# gaius.net
KiCad netlist of a schematic drawn in EAGLE
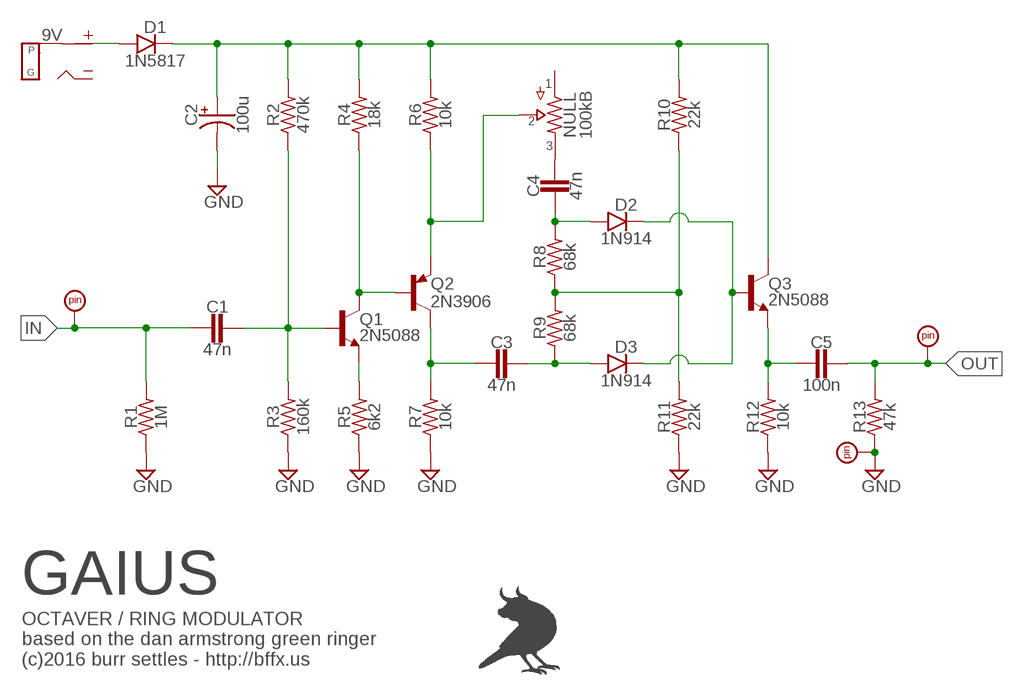
[diagram p0: schematic, sheet 1]

(export (version "E")
  (design (tool "Eeschema 10.0.6"))
  (components
    (comp (ref "9V")
      (value "DC_MONO")
      (footprint "eagle-import:DC")
      (libsource (lib "eagle-import") (part "DC_MONO"))
    )
    (comp (ref "C1")
      (value "47n")
      (footprint "eagle-import:050X030_025_2")
      (libsource (lib "eagle-import") (part "CER/FILM2"))
    )
    (comp (ref "C2")
      (value "100u")
      (footprint "eagle-import:050_020_1")
      (libsource (lib "eagle-import") (part "0501"))
    )
    (comp (ref "C3")
      (value "47n")
      (footprint "eagle-import:050X030_025_2")
      (libsource (lib "eagle-import") (part "CER/FILM2"))
    )
    (comp (ref "C4")
      (value "47n")
      (footprint "eagle-import:050X030_025_2")
      (libsource (lib "eagle-import") (part "CER/FILM2"))
    )
    (comp (ref "C5")
      (value "100n")
      (footprint "eagle-import:050X030_025_2")
      (libsource (lib "eagle-import") (part "CER/FILM2"))
    )
    (comp (ref "D1")
      (value "1N5817")
      (footprint "eagle-import:DO41-3")
      (libsource (lib "eagle-import") (part "DO41.3"))
    )
    (comp (ref "D2")
      (value "1N914")
      (footprint "eagle-import:DO35-2")
      (libsource (lib "eagle-import") (part "DO35.2"))
    )
    (comp (ref "D3")
      (value "1N914")
      (footprint "eagle-import:DO35-2")
      (libsource (lib "eagle-import") (part "DO35.2"))
    )
    (comp (ref "GND")
      (value "PADRND")
      (footprint "eagle-import:ROUND")
      (libsource (lib "eagle-import") (part "PADRND"))
    )
    (comp (ref "IN")
      (value "PADSQR")
      (footprint "eagle-import:SQUARE")
      (libsource (lib "eagle-import") (part "PADSQR"))
    )
    (comp (ref "NULL")
      (value "100kB")
      (footprint "eagle-import:2262_TRIM")
      (libsource (lib "eagle-import") (part "POTSTRIM"))
    )
    (comp (ref "OUT")
      (value "PADSQR")
      (footprint "eagle-import:SQUARE")
      (libsource (lib "eagle-import") (part "PADSQR"))
    )
    (comp (ref "Q1")
      (value "2N5088")
      (footprint "eagle-import:TO92-")
      (libsource (lib "eagle-import") (part "2N5088"))
    )
    (comp (ref "Q2")
      (value "2N3906")
      (footprint "eagle-import:TO92-")
      (libsource (lib "eagle-import") (part "2N3906-"))
    )
    (comp (ref "Q3")
      (value "2N5088")
      (footprint "eagle-import:TO92-")
      (libsource (lib "eagle-import") (part "2N5088"))
    )
    (comp (ref "R1")
      (value "1M")
      (footprint "eagle-import:R0207_3")
      (libsource (lib "eagle-import") (part "R_.3B"))
    )
    (comp (ref "R2")
      (value "470k")
      (footprint "eagle-import:R0207_3")
      (libsource (lib "eagle-import") (part "R_.3B"))
    )
    (comp (ref "R3")
      (value "160k")
      (footprint "eagle-import:R0207_3")
      (libsource (lib "eagle-import") (part "R_.3B"))
    )
    (comp (ref "R4")
      (value "18k")
      (footprint "eagle-import:R0207_3")
      (libsource (lib "eagle-import") (part "R_.3B"))
    )
    (comp (ref "R5")
      (value "6k2")
      (footprint "eagle-import:R0207_3")
      (libsource (lib "eagle-import") (part "R_.3B"))
    )
    (comp (ref "R6")
      (value "10k")
      (footprint "eagle-import:R0207_3")
      (libsource (lib "eagle-import") (part "R_.3B"))
    )
    (comp (ref "R7")
      (value "10k")
      (footprint "eagle-import:R0207_3")
      (libsource (lib "eagle-import") (part "R_.3B"))
    )
    (comp (ref "R8")
      (value "68k")
      (footprint "eagle-import:R0207_3")
      (libsource (lib "eagle-import") (part "R_.3B"))
    )
    (comp (ref "R9")
      (value "68k")
      (footprint "eagle-import:R0207_3")
      (libsource (lib "eagle-import") (part "R_.3B"))
    )
    (comp (ref "R10")
      (value "22k")
      (footprint "eagle-import:R0207_3")
      (libsource (lib "eagle-import") (part "R_.3B"))
    )
    (comp (ref "R11")
      (value "22k")
      (footprint "eagle-import:R0207_3")
      (libsource (lib "eagle-import") (part "R_.3B"))
    )
    (comp (ref "R12")
      (value "10k")
      (footprint "eagle-import:R0207_3")
      (libsource (lib "eagle-import") (part "R_.3B"))
    )
    (comp (ref "R13")
      (value "47k")
      (footprint "eagle-import:R0207_3")
      (libsource (lib "eagle-import") (part "R_.3B"))
    )
  )
  (nets
    (net (code "1") (name "GND") (class "Default")
      (node (ref "C2") (pin "-") (pinfunction "-_-") (pintype "passive"))
      (node (ref "GND") (pin "1") (pinfunction "P$1_1") (pintype "bidirectional"))
      (node (ref "R1") (pin "1") (pinfunction "1_1") (pintype "passive"))
      (node (ref "R11") (pin "1") (pinfunction "1_1") (pintype "passive"))
      (node (ref "R12") (pin "1") (pinfunction "1_1") (pintype "passive"))
      (node (ref "R13") (pin "1") (pinfunction "1_1") (pintype "passive"))
      (node (ref "R3") (pin "1") (pinfunction "1_1") (pintype "passive"))
      (node (ref "R5") (pin "1") (pinfunction "1_1") (pintype "passive"))
      (node (ref "R7") (pin "1") (pinfunction "1_1") (pintype "passive"))
    )
    (net (code "2") (name "IN") (class "Default")
      (node (ref "C1") (pin "2") (pinfunction "2_2") (pintype "passive"))
      (node (ref "IN") (pin "1") (pinfunction "P$1_1") (pintype "bidirectional"))
      (node (ref "R1") (pin "2") (pinfunction "2_2") (pintype "passive"))
    )
    (net (code "3") (name "Net-(9V-TIP)") (class "Default")
      (node (ref "9V") (pin "T") (pinfunction "TIP_T") (pintype "passive"))
      (node (ref "D1") (pin "A") (pinfunction "A_A") (pintype "passive"))
    )
    (net (code "4") (name "Net-(C3-Pad1)") (class "Default")
      (node (ref "C3") (pin "1") (pinfunction "1_1") (pintype "passive"))
      (node (ref "D3") (pin "A") (pinfunction "A_A") (pintype "passive"))
      (node (ref "R9") (pin "1") (pinfunction "1_1") (pintype "passive"))
    )
    (net (code "5") (name "Net-(C4-Pad1)") (class "Default")
      (node (ref "C4") (pin "1") (pinfunction "1_1") (pintype "passive"))
      (node (ref "NULL") (pin "3") (pinfunction "3_3") (pintype "passive"))
    )
    (net (code "6") (name "Net-(C4-Pad2)") (class "Default")
      (node (ref "C4") (pin "2") (pinfunction "2_2") (pintype "passive"))
      (node (ref "D2") (pin "A") (pinfunction "A_A") (pintype "passive"))
      (node (ref "R8") (pin "2") (pinfunction "2_2") (pintype "passive"))
    )
    (net (code "7") (name "Net-(Q1-B)") (class "Default")
      (node (ref "C1") (pin "1") (pinfunction "1_1") (pintype "passive"))
      (node (ref "Q1") (pin "2") (pinfunction "B_2") (pintype "passive"))
      (node (ref "R2") (pin "1") (pinfunction "1_1") (pintype "passive"))
      (node (ref "R3") (pin "2") (pinfunction "2_2") (pintype "passive"))
    )
    (net (code "8") (name "Net-(Q1-C)") (class "Default")
      (node (ref "Q1") (pin "1") (pinfunction "C_1") (pintype "passive"))
      (node (ref "Q2") (pin "2") (pinfunction "B_2") (pintype "passive"))
      (node (ref "R4") (pin "1") (pinfunction "1_1") (pintype "passive"))
    )
    (net (code "9") (name "Net-(Q1-E)") (class "Default")
      (node (ref "Q1") (pin "3") (pinfunction "E_3") (pintype "passive"))
      (node (ref "R5") (pin "2") (pinfunction "2_2") (pintype "passive"))
    )
    (net (code "10") (name "Net-(Q2-C)") (class "Default")
      (node (ref "C3") (pin "2") (pinfunction "2_2") (pintype "passive"))
      (node (ref "Q2") (pin "1") (pinfunction "C_1") (pintype "passive"))
      (node (ref "R7") (pin "2") (pinfunction "2_2") (pintype "passive"))
    )
    (net (code "11") (name "Net-(Q2-E)") (class "Default")
      (node (ref "NULL") (pin "2") (pinfunction "2_2") (pintype "passive"))
      (node (ref "Q2") (pin "3") (pinfunction "E_3") (pintype "passive"))
      (node (ref "R6") (pin "1") (pinfunction "1_1") (pintype "passive"))
    )
    (net (code "12") (name "Net-(Q3-B)") (class "Default")
      (node (ref "D2") (pin "C") (pinfunction "C_C") (pintype "passive"))
      (node (ref "D3") (pin "C") (pinfunction "C_C") (pintype "passive"))
      (node (ref "Q3") (pin "2") (pinfunction "B_2") (pintype "passive"))
    )
    (net (code "13") (name "Net-(Q3-C)") (class "Default")
      (node (ref "C2") (pin "+") (pinfunction "+_+") (pintype "passive"))
      (node (ref "D1") (pin "C") (pinfunction "C_C") (pintype "passive"))
      (node (ref "Q3") (pin "1") (pinfunction "C_1") (pintype "passive"))
      (node (ref "R10") (pin "2") (pinfunction "2_2") (pintype "passive"))
      (node (ref "R2") (pin "2") (pinfunction "2_2") (pintype "passive"))
      (node (ref "R4") (pin "2") (pinfunction "2_2") (pintype "passive"))
      (node (ref "R6") (pin "2") (pinfunction "2_2") (pintype "passive"))
    )
    (net (code "14") (name "Net-(Q3-E)") (class "Default")
      (node (ref "C5") (pin "2") (pinfunction "2_2") (pintype "passive"))
      (node (ref "Q3") (pin "3") (pinfunction "E_3") (pintype "passive"))
      (node (ref "R12") (pin "2") (pinfunction "2_2") (pintype "passive"))
    )
    (net (code "15") (name "Net-(R10-Pad1)") (class "Default")
      (node (ref "R10") (pin "1") (pinfunction "1_1") (pintype "passive"))
      (node (ref "R11") (pin "2") (pinfunction "2_2") (pintype "passive"))
      (node (ref "R8") (pin "1") (pinfunction "1_1") (pintype "passive"))
      (node (ref "R9") (pin "2") (pinfunction "2_2") (pintype "passive"))
    )
    (net (code "16") (name "OUT") (class "Default")
      (node (ref "C5") (pin "1") (pinfunction "1_1") (pintype "passive"))
      (node (ref "OUT") (pin "1") (pinfunction "P$1_1") (pintype "bidirectional"))
      (node (ref "R13") (pin "2") (pinfunction "2_2") (pintype "passive"))
    )
    (net (code "17") (name "unconnected-(9V-SLEEVE-PadS)") (class "Default")
      (node (ref "9V") (pin "S") (pinfunction "SLEEVE_S") (pintype "passive"))
    )
    (net (code "18") (name "unconnected-(NULL-Pad1)") (class "Default")
      (node (ref "NULL") (pin "1") (pinfunction "1_1") (pintype "passive"))
    )
  )
)
